# Rotating_Section.net
KiCad netlist of a schematic drawn in EAGLE
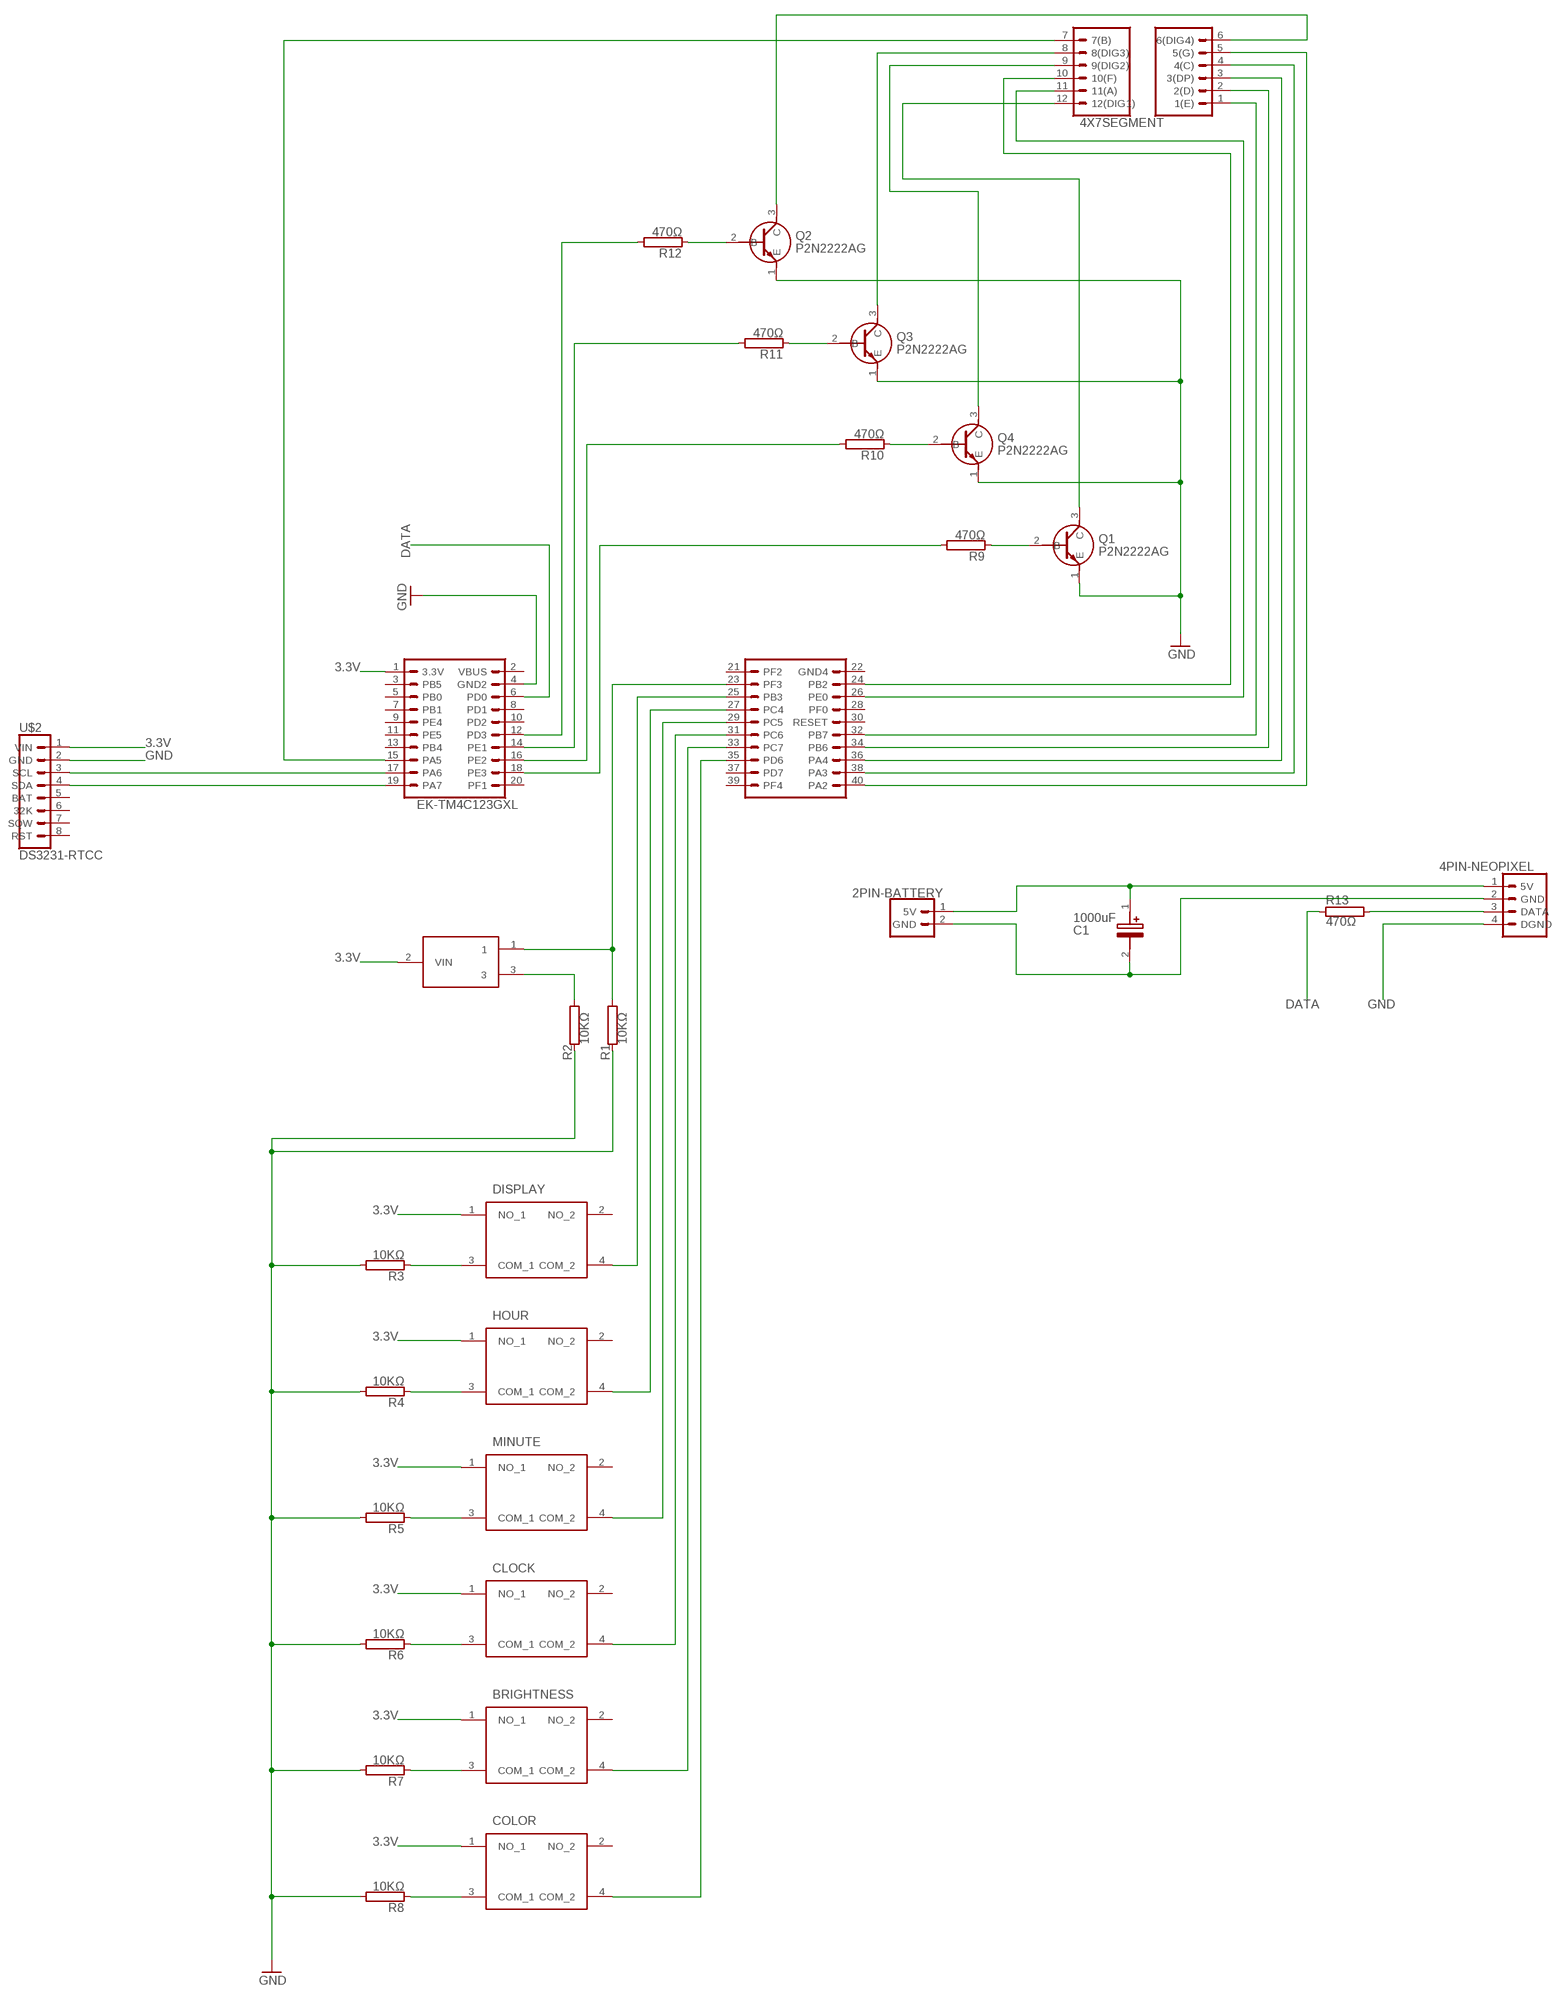
[diagram p0: schematic, sheet 1]

(export (version "E")
  (design (tool "Eeschema 10.0.6"))
  (components
    (comp (ref "BRIGHTNESS")
      (value "PTS645SL432LFS")
      (footprint "eagle-import:PTS645SL432LFS")
      (fields (field (name "MOUSER_PART_NUMBER") "611-PTS645SL432"))
      (libsource (lib "eagle-import") (part "PTS645SL432LFS"))
    )
    (comp (ref "C1")
      (value "1000uF")
      (footprint "eagle-import:CAPPRD500W65D1250H2200")
      (fields
        (field (name "MANUFACTURER_PART_NUMBER") "EEU-FP1V102")
        (field (name "MOUSER_PART_NUMBER") "667-EEU-FP1V102")
      )
      (libsource (lib "eagle-import") (part "EEU-FP1V102"))
    )
    (comp (ref "CLOCK")
      (value "PTS645SL432LFS")
      (footprint "eagle-import:PTS645SL432LFS")
      (fields (field (name "MOUSER_PART_NUMBER") "611-PTS645SL432"))
      (libsource (lib "eagle-import") (part "PTS645SL432LFS"))
    )
    (comp (ref "COLOR")
      (value "PTS645SL432LFS")
      (footprint "eagle-import:PTS645SL432LFS")
      (fields (field (name "MOUSER_PART_NUMBER") "611-PTS645SL432"))
      (libsource (lib "eagle-import") (part "PTS645SL432LFS"))
    )
    (comp (ref "DISPLAY")
      (value "PTS645SL432LFS")
      (footprint "eagle-import:PTS645SL432LFS")
      (fields (field (name "MOUSER_PART_NUMBER") "611-PTS645SL432"))
      (libsource (lib "eagle-import") (part "PTS645SL432LFS"))
    )
    (comp (ref "HOUR")
      (value "PTS645SL432LFS")
      (footprint "eagle-import:PTS645SL432LFS")
      (fields (field (name "MOUSER_PART_NUMBER") "611-PTS645SL432"))
      (libsource (lib "eagle-import") (part "PTS645SL432LFS"))
    )
    (comp (ref "MINUTE")
      (value "PTS645SL432LFS")
      (footprint "eagle-import:PTS645SL432LFS")
      (fields (field (name "MOUSER_PART_NUMBER") "611-PTS645SL432"))
      (libsource (lib "eagle-import") (part "PTS645SL432LFS"))
    )
    (comp (ref "Q1")
      (value "P2N2222AG")
      (footprint "eagle-import:TO-92")
      (fields (field (name "MOUSER_PART_NUMBER") "863-P2N2222AG"))
      (libsource (lib "eagle-import") (part "P2N2222AG"))
    )
    (comp (ref "Q2")
      (value "P2N2222AG")
      (footprint "eagle-import:TO-92")
      (fields (field (name "MOUSER_PART_NUMBER") "863-P2N2222AG"))
      (libsource (lib "eagle-import") (part "P2N2222AG"))
    )
    (comp (ref "Q3")
      (value "P2N2222AG")
      (footprint "eagle-import:TO-92")
      (fields (field (name "MOUSER_PART_NUMBER") "863-P2N2222AG"))
      (libsource (lib "eagle-import") (part "P2N2222AG"))
    )
    (comp (ref "Q4")
      (value "P2N2222AG")
      (footprint "eagle-import:TO-92")
      (fields (field (name "MOUSER_PART_NUMBER") "863-P2N2222AG"))
      (libsource (lib "eagle-import") (part "P2N2222AG"))
    )
    (comp (ref "R1")
      (value "10KΩ")
      (footprint "eagle-import:TO-247-2V")
      (libsource (lib "eagle-import") (part "RMG100-V"))
    )
    (comp (ref "R2")
      (value "10KΩ")
      (footprint "eagle-import:TO-247-2V")
      (libsource (lib "eagle-import") (part "RMG100-V"))
    )
    (comp (ref "R3")
      (value "10KΩ")
      (footprint "eagle-import:TO-247-2V")
      (libsource (lib "eagle-import") (part "RMG100-V"))
    )
    (comp (ref "R4")
      (value "10KΩ")
      (footprint "eagle-import:TO-247-2V")
      (libsource (lib "eagle-import") (part "RMG100-V"))
    )
    (comp (ref "R5")
      (value "10KΩ")
      (footprint "eagle-import:TO-247-2V")
      (libsource (lib "eagle-import") (part "RMG100-V"))
    )
    (comp (ref "R6")
      (value "10KΩ")
      (footprint "eagle-import:TO-247-2V")
      (libsource (lib "eagle-import") (part "RMG100-V"))
    )
    (comp (ref "R7")
      (value "10KΩ")
      (footprint "eagle-import:TO-247-2V")
      (libsource (lib "eagle-import") (part "RMG100-V"))
    )
    (comp (ref "R8")
      (value "10KΩ")
      (footprint "eagle-import:TO-247-2V")
      (libsource (lib "eagle-import") (part "RMG100-V"))
    )
    (comp (ref "R9")
      (value "470Ω")
      (footprint "eagle-import:TO-247-2V")
      (libsource (lib "eagle-import") (part "RMG100-V"))
    )
    (comp (ref "R10")
      (value "470Ω")
      (footprint "eagle-import:TO-247-2V")
      (libsource (lib "eagle-import") (part "RMG100-V"))
    )
    (comp (ref "R11")
      (value "470Ω")
      (footprint "eagle-import:TO-247-2V")
      (libsource (lib "eagle-import") (part "RMG100-V"))
    )
    (comp (ref "R12")
      (value "470Ω")
      (footprint "eagle-import:TO-247-2V")
      (libsource (lib "eagle-import") (part "RMG100-V"))
    )
    (comp (ref "R13")
      (value "470Ω")
      (footprint "eagle-import:TO-247-2V")
      (libsource (lib "eagle-import") (part "RMG100-V"))
    )
    (comp (ref "S1")
      (value "1101M2S3CQE2")
      (footprint "eagle-import:1000-SERIES(SPDT)")
      (fields (field (name "MOUSER_PART_NUMBER") "611-1101M2S3CQE2"))
      (libsource (lib "eagle-import") (part "1101M2S3CQE2"))
    )
    (comp (ref "U$1")
      (value "4X7SEGMENT")
      (footprint "eagle-import:4X7SEGMENT")
      (libsource (lib "eagle-import") (part "4X7SEGMENT"))
    )
    (comp (ref "U$2")
      (value "DS3231-RTCC")
      (footprint "eagle-import:1X08")
      (libsource (lib "eagle-import") (part "DS3231-RTCC"))
    )
    (comp (ref "U$3")
      (value "EK-TM4C123GXL")
      (footprint "eagle-import:EK-TM4C123GXL")
      (libsource (lib "eagle-import") (part "EK-TM4C123GXL"))
    )
    (comp (ref "U$4")
      (value "4PIN-NEOPIXEL")
      (footprint "eagle-import:4PIN-NEOPIXEL")
      (libsource (lib "eagle-import") (part "4PIN-NEOPIXEL"))
    )
    (comp (ref "U$5")
      (value "2PIN-BATTERY")
      (footprint "eagle-import:2PIN-BATTERY")
      (libsource (lib "eagle-import") (part "2PIN-BATTERY"))
    )
  )
  (nets
    (net (code "1") (name "/3.3V") (class "Default")
      (node (ref "BRIGHTNESS") (pin "1") (pinfunction "NO_1_1") (pintype "bidirectional"))
      (node (ref "CLOCK") (pin "1") (pinfunction "NO_1_1") (pintype "bidirectional"))
      (node (ref "COLOR") (pin "1") (pinfunction "NO_1_1") (pintype "bidirectional"))
      (node (ref "DISPLAY") (pin "1") (pinfunction "NO_1_1") (pintype "bidirectional"))
      (node (ref "HOUR") (pin "1") (pinfunction "NO_1_1") (pintype "bidirectional"))
      (node (ref "MINUTE") (pin "1") (pinfunction "NO_1_1") (pintype "bidirectional"))
      (node (ref "S1") (pin "2") (pinfunction "VIN_2") (pintype "power_in"))
      (node (ref "U$2") (pin "1") (pinfunction "VIN_1") (pintype "power_in"))
      (node (ref "U$3") (pin "1") (pinfunction "3.3V_1") (pintype "power_in"))
    )
    (net (code "2") (name "/BAT") (class "Default")
      (node (ref "U$2") (pin "5") (pinfunction "BAT_5") (pintype "power_in"))
    )
    (net (code "3") (name "/DATA") (class "Default")
      (node (ref "R13") (pin "1") (pinfunction "1_1") (pintype "passive"))
      (node (ref "U$3") (pin "6") (pinfunction "PD0_6") (pintype "bidirectional"))
    )
    (net (code "4") (name "/GND4") (class "Default")
      (node (ref "U$3") (pin "22") (pinfunction "GND4_22") (pintype "power_in"))
    )
    (net (code "5") (name "/VBUS") (class "Default")
      (node (ref "U$3") (pin "2") (pinfunction "VBUS_2") (pintype "power_in"))
    )
    (net (code "6") (name "GND") (class "Default")
      (node (ref "Q1") (pin "1") (pinfunction "E_1") (pintype "bidirectional"))
      (node (ref "Q2") (pin "1") (pinfunction "E_1") (pintype "bidirectional"))
      (node (ref "Q3") (pin "1") (pinfunction "E_1") (pintype "bidirectional"))
      (node (ref "Q4") (pin "1") (pinfunction "E_1") (pintype "bidirectional"))
      (node (ref "R1") (pin "1") (pinfunction "1_1") (pintype "passive"))
      (node (ref "R2") (pin "1") (pinfunction "1_1") (pintype "passive"))
      (node (ref "R3") (pin "2") (pinfunction "2_2") (pintype "passive"))
      (node (ref "R4") (pin "2") (pinfunction "2_2") (pintype "passive"))
      (node (ref "R5") (pin "2") (pinfunction "2_2") (pintype "passive"))
      (node (ref "R6") (pin "2") (pinfunction "2_2") (pintype "passive"))
      (node (ref "R7") (pin "2") (pinfunction "2_2") (pintype "passive"))
      (node (ref "R8") (pin "2") (pinfunction "2_2") (pintype "passive"))
      (node (ref "U$2") (pin "2") (pinfunction "GND_2") (pintype "power_in"))
      (node (ref "U$3") (pin "4") (pinfunction "GND2_4") (pintype "power_in"))
      (node (ref "U$4") (pin "4") (pinfunction "DGND_4") (pintype "bidirectional"))
    )
    (net (code "7") (name "Net-(BRIGHTNESS-COM_1)") (class "Default")
      (node (ref "BRIGHTNESS") (pin "3") (pinfunction "COM_1_3") (pintype "bidirectional"))
      (node (ref "R7") (pin "1") (pinfunction "1_1") (pintype "passive"))
    )
    (net (code "8") (name "Net-(BRIGHTNESS-COM_2)") (class "Default")
      (node (ref "BRIGHTNESS") (pin "4") (pinfunction "COM_2_4") (pintype "bidirectional"))
      (node (ref "U$3") (pin "33") (pinfunction "PC7_33") (pintype "bidirectional"))
    )
    (net (code "9") (name "Net-(C1-+)") (class "Default")
      (node (ref "C1") (pin "1") (pinfunction "+_1") (pintype "bidirectional"))
      (node (ref "U$4") (pin "1") (pinfunction "5V_1") (pintype "bidirectional"))
      (node (ref "U$5") (pin "1") (pinfunction "5V_1") (pintype "input"))
    )
    (net (code "10") (name "Net-(C1--)") (class "Default")
      (node (ref "C1") (pin "2") (pinfunction "-_2") (pintype "bidirectional"))
      (node (ref "U$4") (pin "2") (pinfunction "GND_2") (pintype "bidirectional"))
      (node (ref "U$5") (pin "2") (pinfunction "GND_2") (pintype "passive"))
    )
    (net (code "11") (name "Net-(CLOCK-COM_1)") (class "Default")
      (node (ref "CLOCK") (pin "3") (pinfunction "COM_1_3") (pintype "bidirectional"))
      (node (ref "R6") (pin "1") (pinfunction "1_1") (pintype "passive"))
    )
    (net (code "12") (name "Net-(CLOCK-COM_2)") (class "Default")
      (node (ref "CLOCK") (pin "4") (pinfunction "COM_2_4") (pintype "bidirectional"))
      (node (ref "U$3") (pin "31") (pinfunction "PC6_31") (pintype "bidirectional"))
    )
    (net (code "13") (name "Net-(COLOR-COM_1)") (class "Default")
      (node (ref "COLOR") (pin "3") (pinfunction "COM_1_3") (pintype "bidirectional"))
      (node (ref "R8") (pin "1") (pinfunction "1_1") (pintype "passive"))
    )
    (net (code "14") (name "Net-(COLOR-COM_2)") (class "Default")
      (node (ref "COLOR") (pin "4") (pinfunction "COM_2_4") (pintype "bidirectional"))
      (node (ref "U$3") (pin "35") (pinfunction "PD6_35") (pintype "bidirectional"))
    )
    (net (code "15") (name "Net-(DISPLAY-COM_1)") (class "Default")
      (node (ref "DISPLAY") (pin "3") (pinfunction "COM_1_3") (pintype "bidirectional"))
      (node (ref "R3") (pin "1") (pinfunction "1_1") (pintype "passive"))
    )
    (net (code "16") (name "Net-(DISPLAY-COM_2)") (class "Default")
      (node (ref "DISPLAY") (pin "4") (pinfunction "COM_2_4") (pintype "bidirectional"))
      (node (ref "U$3") (pin "25") (pinfunction "PB3_25") (pintype "bidirectional"))
    )
    (net (code "17") (name "Net-(HOUR-COM_1)") (class "Default")
      (node (ref "HOUR") (pin "3") (pinfunction "COM_1_3") (pintype "bidirectional"))
      (node (ref "R4") (pin "1") (pinfunction "1_1") (pintype "passive"))
    )
    (net (code "18") (name "Net-(HOUR-COM_2)") (class "Default")
      (node (ref "HOUR") (pin "4") (pinfunction "COM_2_4") (pintype "bidirectional"))
      (node (ref "U$3") (pin "27") (pinfunction "PC4_27") (pintype "bidirectional"))
    )
    (net (code "19") (name "Net-(MINUTE-COM_1)") (class "Default")
      (node (ref "MINUTE") (pin "3") (pinfunction "COM_1_3") (pintype "bidirectional"))
      (node (ref "R5") (pin "1") (pinfunction "1_1") (pintype "passive"))
    )
    (net (code "20") (name "Net-(MINUTE-COM_2)") (class "Default")
      (node (ref "MINUTE") (pin "4") (pinfunction "COM_2_4") (pintype "bidirectional"))
      (node (ref "U$3") (pin "29") (pinfunction "PC5_29") (pintype "bidirectional"))
    )
    (net (code "21") (name "Net-(Q1-B)") (class "Default")
      (node (ref "Q1") (pin "2") (pinfunction "B_2") (pintype "bidirectional"))
      (node (ref "R9") (pin "1") (pinfunction "1_1") (pintype "passive"))
    )
    (net (code "22") (name "Net-(Q1-C)") (class "Default")
      (node (ref "Q1") (pin "3") (pinfunction "C_3") (pintype "bidirectional"))
      (node (ref "U$1") (pin "12") (pinfunction "12(DIG1)_12") (pintype "input"))
    )
    (net (code "23") (name "Net-(Q2-B)") (class "Default")
      (node (ref "Q2") (pin "2") (pinfunction "B_2") (pintype "bidirectional"))
      (node (ref "R12") (pin "1") (pinfunction "1_1") (pintype "passive"))
    )
    (net (code "24") (name "Net-(Q2-C)") (class "Default")
      (node (ref "Q2") (pin "3") (pinfunction "C_3") (pintype "bidirectional"))
      (node (ref "U$1") (pin "6") (pinfunction "6(DIG4)_6") (pintype "input"))
    )
    (net (code "25") (name "Net-(Q3-B)") (class "Default")
      (node (ref "Q3") (pin "2") (pinfunction "B_2") (pintype "bidirectional"))
      (node (ref "R11") (pin "1") (pinfunction "1_1") (pintype "passive"))
    )
    (net (code "26") (name "Net-(Q3-C)") (class "Default")
      (node (ref "Q3") (pin "3") (pinfunction "C_3") (pintype "bidirectional"))
      (node (ref "U$1") (pin "8") (pinfunction "8(DIG3)_8") (pintype "input"))
    )
    (net (code "27") (name "Net-(Q4-B)") (class "Default")
      (node (ref "Q4") (pin "2") (pinfunction "B_2") (pintype "bidirectional"))
      (node (ref "R10") (pin "1") (pinfunction "1_1") (pintype "passive"))
    )
    (net (code "28") (name "Net-(Q4-C)") (class "Default")
      (node (ref "Q4") (pin "3") (pinfunction "C_3") (pintype "bidirectional"))
      (node (ref "U$1") (pin "9") (pinfunction "9(DIG2)_9") (pintype "input"))
    )
    (net (code "29") (name "Net-(R2-Pad2)") (class "Default")
      (node (ref "R2") (pin "2") (pinfunction "2_2") (pintype "passive"))
      (node (ref "S1") (pin "3") (pinfunction "3_3") (pintype "output"))
    )
    (net (code "30") (name "Net-(U$1-1(E))") (class "Default")
      (node (ref "U$1") (pin "1") (pinfunction "1(E)_1") (pintype "input"))
      (node (ref "U$3") (pin "32") (pinfunction "PB7_32") (pintype "bidirectional"))
    )
    (net (code "31") (name "Net-(U$1-2(D))") (class "Default")
      (node (ref "U$1") (pin "2") (pinfunction "2(D)_2") (pintype "input"))
      (node (ref "U$3") (pin "34") (pinfunction "PB6_34") (pintype "bidirectional"))
    )
    (net (code "32") (name "Net-(U$1-3(DP))") (class "Default")
      (node (ref "U$1") (pin "3") (pinfunction "3(DP)_3") (pintype "input"))
      (node (ref "U$3") (pin "36") (pinfunction "PA4_36") (pintype "bidirectional"))
    )
    (net (code "33") (name "Net-(U$1-4(C))") (class "Default")
      (node (ref "U$1") (pin "4") (pinfunction "4(C)_4") (pintype "input"))
      (node (ref "U$3") (pin "38") (pinfunction "PA3_38") (pintype "bidirectional"))
    )
    (net (code "34") (name "Net-(U$1-5(G))") (class "Default")
      (node (ref "U$1") (pin "5") (pinfunction "5(G)_5") (pintype "input"))
      (node (ref "U$3") (pin "40") (pinfunction "PA2_40") (pintype "bidirectional"))
    )
    (net (code "35") (name "Net-(U$1-7(B))") (class "Default")
      (node (ref "U$1") (pin "7") (pinfunction "7(B)_7") (pintype "input"))
      (node (ref "U$3") (pin "15") (pinfunction "PA5_15") (pintype "bidirectional"))
    )
    (net (code "36") (name "Net-(U$1-10(F))") (class "Default")
      (node (ref "U$1") (pin "10") (pinfunction "10(F)_10") (pintype "input"))
      (node (ref "U$3") (pin "24") (pinfunction "PB2_24") (pintype "bidirectional"))
    )
    (net (code "37") (name "Net-(U$1-11(A))") (class "Default")
      (node (ref "U$1") (pin "11") (pinfunction "11(A)_11") (pintype "input"))
      (node (ref "U$3") (pin "26") (pinfunction "PE0_26") (pintype "bidirectional"))
    )
    (net (code "38") (name "Net-(U$2-SCL)") (class "Default")
      (node (ref "U$2") (pin "3") (pinfunction "SCL_3") (pintype "bidirectional"))
      (node (ref "U$3") (pin "17") (pinfunction "PA6_17") (pintype "bidirectional"))
    )
    (net (code "39") (name "Net-(U$2-SDA)") (class "Default")
      (node (ref "U$2") (pin "4") (pinfunction "SDA_4") (pintype "bidirectional"))
      (node (ref "U$3") (pin "19") (pinfunction "PA7_19") (pintype "bidirectional"))
    )
    (net (code "40") (name "Net-(U$3-PD3)") (class "Default")
      (node (ref "R12") (pin "2") (pinfunction "2_2") (pintype "passive"))
      (node (ref "U$3") (pin "12") (pinfunction "PD3_12") (pintype "bidirectional"))
    )
    (net (code "41") (name "Net-(U$3-PE1)") (class "Default")
      (node (ref "R11") (pin "2") (pinfunction "2_2") (pintype "passive"))
      (node (ref "U$3") (pin "14") (pinfunction "PE1_14") (pintype "bidirectional"))
    )
    (net (code "42") (name "Net-(U$3-PE2)") (class "Default")
      (node (ref "R10") (pin "2") (pinfunction "2_2") (pintype "passive"))
      (node (ref "U$3") (pin "16") (pinfunction "PE2_16") (pintype "bidirectional"))
    )
    (net (code "43") (name "Net-(U$3-PE3)") (class "Default")
      (node (ref "R9") (pin "2") (pinfunction "2_2") (pintype "passive"))
      (node (ref "U$3") (pin "18") (pinfunction "PE3_18") (pintype "bidirectional"))
    )
    (net (code "44") (name "Net-(U$3-PF3)") (class "Default")
      (node (ref "R1") (pin "2") (pinfunction "2_2") (pintype "passive"))
      (node (ref "S1") (pin "1") (pinfunction "1_1") (pintype "output"))
      (node (ref "U$3") (pin "23") (pinfunction "PF3_23") (pintype "bidirectional"))
    )
    (net (code "45") (name "Net-(U$4-DATA)") (class "Default")
      (node (ref "R13") (pin "2") (pinfunction "2_2") (pintype "passive"))
      (node (ref "U$4") (pin "3") (pinfunction "DATA_3") (pintype "bidirectional"))
    )
    (net (code "46") (name "unconnected-(BRIGHTNESS-NO_2-Pad2)") (class "Default")
      (node (ref "BRIGHTNESS") (pin "2") (pinfunction "NO_2_2") (pintype "bidirectional"))
    )
    (net (code "47") (name "unconnected-(CLOCK-NO_2-Pad2)") (class "Default")
      (node (ref "CLOCK") (pin "2") (pinfunction "NO_2_2") (pintype "bidirectional"))
    )
    (net (code "48") (name "unconnected-(COLOR-NO_2-Pad2)") (class "Default")
      (node (ref "COLOR") (pin "2") (pinfunction "NO_2_2") (pintype "bidirectional"))
    )
    (net (code "49") (name "unconnected-(DISPLAY-NO_2-Pad2)") (class "Default")
      (node (ref "DISPLAY") (pin "2") (pinfunction "NO_2_2") (pintype "bidirectional"))
    )
    (net (code "50") (name "unconnected-(HOUR-NO_2-Pad2)") (class "Default")
      (node (ref "HOUR") (pin "2") (pinfunction "NO_2_2") (pintype "bidirectional"))
    )
    (net (code "51") (name "unconnected-(MINUTE-NO_2-Pad2)") (class "Default")
      (node (ref "MINUTE") (pin "2") (pinfunction "NO_2_2") (pintype "bidirectional"))
    )
    (net (code "52") (name "unconnected-(U$2-32K-Pad6)") (class "Default")
      (node (ref "U$2") (pin "6") (pinfunction "32K_6") (pintype "bidirectional"))
    )
    (net (code "53") (name "unconnected-(U$2-RST-Pad8)") (class "Default")
      (node (ref "U$2") (pin "8") (pinfunction "RST_8") (pintype "bidirectional"))
    )
    (net (code "54") (name "unconnected-(U$2-SQW-Pad7)") (class "Default")
      (node (ref "U$2") (pin "7") (pinfunction "SQW_7") (pintype "bidirectional"))
    )
    (net (code "55") (name "unconnected-(U$3-PB0-Pad5)") (class "Default")
      (node (ref "U$3") (pin "5") (pinfunction "PB0_5") (pintype "bidirectional"))
    )
    (net (code "56") (name "unconnected-(U$3-PB1-Pad7)") (class "Default")
      (node (ref "U$3") (pin "7") (pinfunction "PB1_7") (pintype "bidirectional"))
    )
    (net (code "57") (name "unconnected-(U$3-PB4-Pad13)") (class "Default")
      (node (ref "U$3") (pin "13") (pinfunction "PB4_13") (pintype "bidirectional"))
    )
    (net (code "58") (name "unconnected-(U$3-PB5-Pad3)") (class "Default")
      (node (ref "U$3") (pin "3") (pinfunction "PB5_3") (pintype "bidirectional"))
    )
    (net (code "59") (name "unconnected-(U$3-PD1-Pad8)") (class "Default")
      (node (ref "U$3") (pin "8") (pinfunction "PD1_8") (pintype "bidirectional"))
    )
    (net (code "60") (name "unconnected-(U$3-PD2-Pad10)") (class "Default")
      (node (ref "U$3") (pin "10") (pinfunction "PD2_10") (pintype "bidirectional"))
    )
    (net (code "61") (name "unconnected-(U$3-PD7-Pad37)") (class "Default")
      (node (ref "U$3") (pin "37") (pinfunction "PD7_37") (pintype "bidirectional"))
    )
    (net (code "62") (name "unconnected-(U$3-PE4-Pad9)") (class "Default")
      (node (ref "U$3") (pin "9") (pinfunction "PE4_9") (pintype "bidirectional"))
    )
    (net (code "63") (name "unconnected-(U$3-PE5-Pad11)") (class "Default")
      (node (ref "U$3") (pin "11") (pinfunction "PE5_11") (pintype "bidirectional"))
    )
    (net (code "64") (name "unconnected-(U$3-PF0-Pad28)") (class "Default")
      (node (ref "U$3") (pin "28") (pinfunction "PF0_28") (pintype "bidirectional"))
    )
    (net (code "65") (name "unconnected-(U$3-PF1-Pad20)") (class "Default")
      (node (ref "U$3") (pin "20") (pinfunction "PF1_20") (pintype "bidirectional"))
    )
    (net (code "66") (name "unconnected-(U$3-PF2-Pad21)") (class "Default")
      (node (ref "U$3") (pin "21") (pinfunction "PF2_21") (pintype "bidirectional"))
    )
    (net (code "67") (name "unconnected-(U$3-PF4-Pad39)") (class "Default")
      (node (ref "U$3") (pin "39") (pinfunction "PF4_39") (pintype "bidirectional"))
    )
    (net (code "68") (name "unconnected-(U$3-RESET-Pad30)") (class "Default")
      (node (ref "U$3") (pin "30") (pinfunction "RESET_30") (pintype "input"))
    )
  )
)
